# drvinput2.net
KiCad netlist of a schematic drawn in Altium Designer
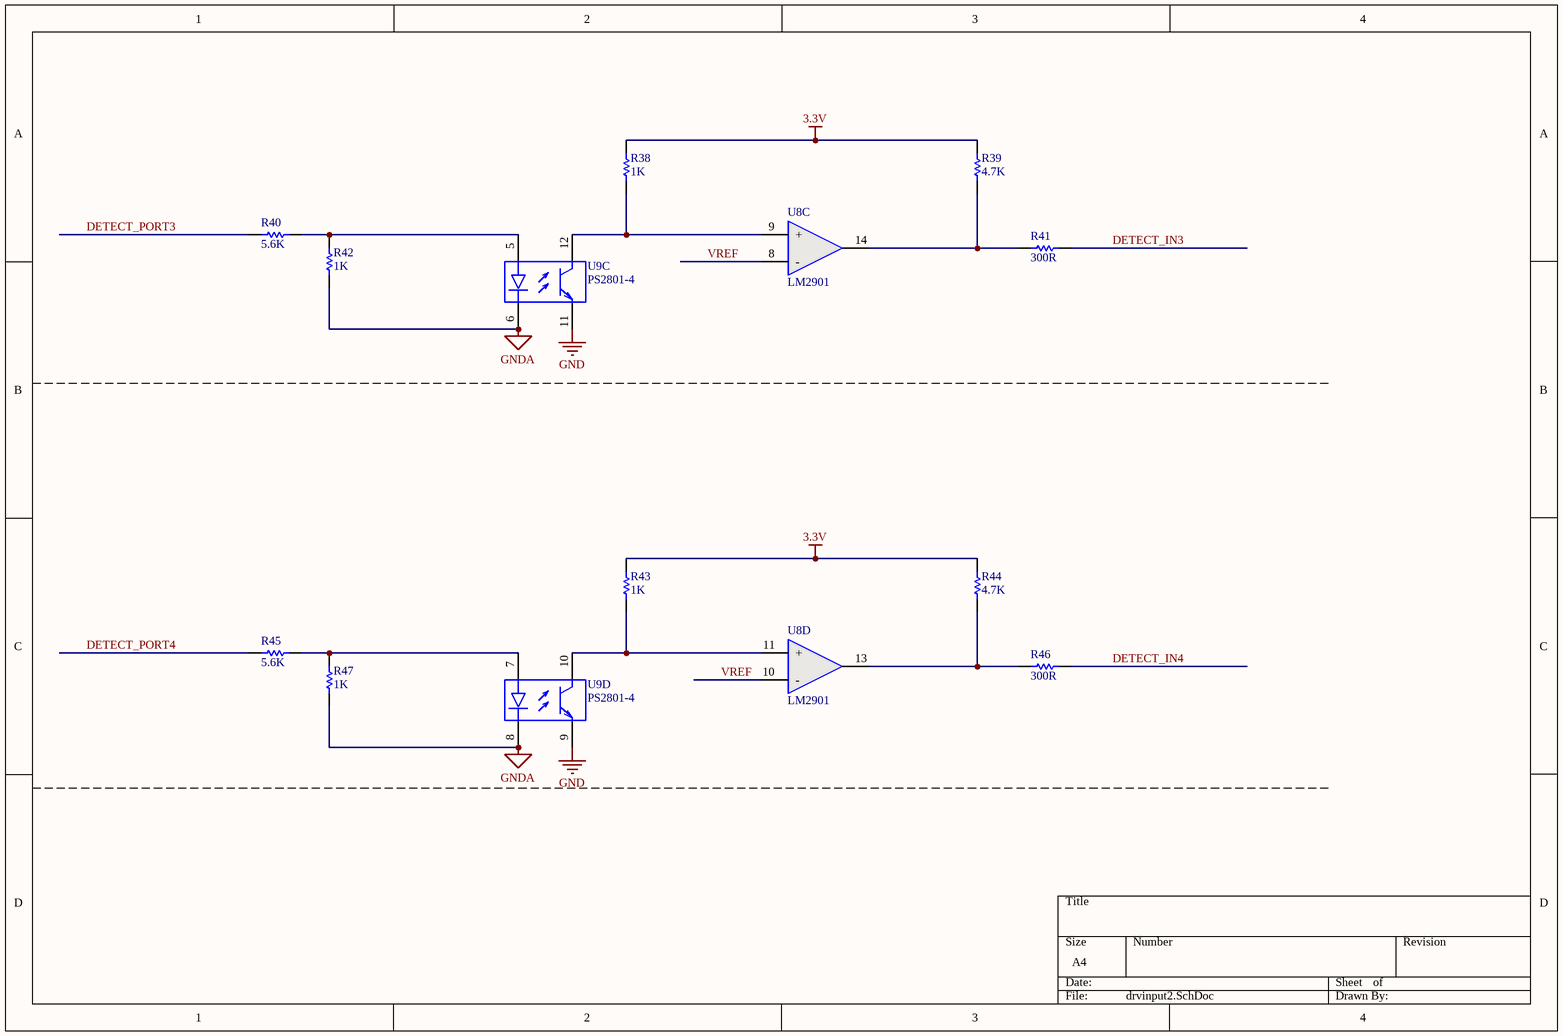
[diagram p0: drvinput2.SchDoc]

(export (version "E")
  (design (tool "Eeschema 10.0.6"))
  (components
    (comp (ref "R38")
      (value "1K")
      (footprint "RESC2012M")
      (description "Resistor")
      (fields (field (name "PUBLISHER") "Altium Limited"))
      (libsource (lib "Miscellaneous Devices") (part "Res1"))
    )
    (comp (ref "R39")
      (value "4.7K")
      (footprint "RESC2012M")
      (description "Resistor")
      (fields (field (name "PUBLISHER") "Altium Limited"))
      (libsource (lib "Miscellaneous Devices") (part "Res1"))
    )
    (comp (ref "R40")
      (value "5.6K")
      (footprint "RESC2012M")
      (description "Resistor")
      (fields (field (name "PUBLISHER") "Altium Limited"))
      (libsource (lib "Miscellaneous Devices") (part "Res1"))
    )
    (comp (ref "R41")
      (value "300R")
      (footprint "RESC2012M")
      (description "Resistor")
      (fields (field (name "PUBLISHER") "Altium Limited"))
      (libsource (lib "Miscellaneous Devices") (part "Res1"))
    )
    (comp (ref "R42")
      (value "1K")
      (footprint "RESC2012M")
      (description "Resistor")
      (fields (field (name "PUBLISHER") "Altium Limited"))
      (libsource (lib "Miscellaneous Devices") (part "Res1"))
    )
    (comp (ref "R43")
      (value "1K")
      (footprint "RESC2012M")
      (description "Resistor")
      (fields (field (name "PUBLISHER") "Altium Limited"))
      (libsource (lib "Miscellaneous Devices") (part "Res1"))
    )
    (comp (ref "R44")
      (value "4.7K")
      (footprint "RESC2012M")
      (description "Resistor")
      (fields (field (name "PUBLISHER") "Altium Limited"))
      (libsource (lib "Miscellaneous Devices") (part "Res1"))
    )
    (comp (ref "R45")
      (value "5.6K")
      (footprint "RESC2012M")
      (description "Resistor")
      (fields (field (name "PUBLISHER") "Altium Limited"))
      (libsource (lib "Miscellaneous Devices") (part "Res1"))
    )
    (comp (ref "R46")
      (value "300R")
      (footprint "RESC2012M")
      (description "Resistor")
      (fields (field (name "PUBLISHER") "Altium Limited"))
      (libsource (lib "Miscellaneous Devices") (part "Res1"))
    )
    (comp (ref "R47")
      (value "1K")
      (footprint "RESC2012M")
      (description "Resistor")
      (fields (field (name "PUBLISHER") "Altium Limited"))
      (libsource (lib "Miscellaneous Devices") (part "Res1"))
    )
    (comp (ref "U8")
      (value "LM2901")
      (footprint "SOIC-14AM")
      (description "4通道差分比较器芯片")
      (libsource (lib "UserSchDev") (part "LM2901"))
    )
    (comp (ref "U9")
      (value "PS2801-4")
      (footprint "SOIC16_N")
      (fields (field (name "PUBLISHER") "Altium Limited"))
      (libsource (lib "UserSchDev") (part "PS2801-4"))
    )
  )
  (nets
    (net (code "1") (name "/DETECT_IN3") (class "Default")
      (node (ref "R41") (pin "1") (pinfunction "1_1") (pintype "passive"))
    )
    (net (code "2") (name "/DETECT_IN4") (class "Default")
      (node (ref "R46") (pin "2") (pinfunction "2_2") (pintype "passive"))
    )
    (net (code "3") (name "/DETECT_PORT3") (class "Default")
      (node (ref "R40") (pin "2") (pinfunction "2_2") (pintype "passive"))
    )
    (net (code "4") (name "/DETECT_PORT4") (class "Default")
      (node (ref "R45") (pin "2") (pinfunction "2_2") (pintype "passive"))
    )
    (net (code "5") (name "/VREF") (class "Default")
      (node (ref "U8") (pin "10") (pinfunction "-_10") (pintype "passive"))
      (node (ref "U8") (pin "8") (pinfunction "-_8") (pintype "passive"))
    )
    (net (code "6") (name "3.3V") (class "Default")
      (node (ref "R38") (pin "1") (pinfunction "1_1") (pintype "passive"))
      (node (ref "R39") (pin "2") (pinfunction "2_2") (pintype "passive"))
      (node (ref "R43") (pin "1") (pinfunction "1_1") (pintype "passive"))
      (node (ref "R44") (pin "2") (pinfunction "2_2") (pintype "passive"))
    )
    (net (code "7") (name "GND") (class "Default")
      (node (ref "U9") (pin "11") (pinfunction "E_11") (pintype "passive"))
      (node (ref "U9") (pin "9") (pinfunction "E_9") (pintype "passive"))
    )
    (net (code "8") (name "GNDA") (class "Default")
      (node (ref "R42") (pin "1") (pinfunction "1_1") (pintype "passive"))
      (node (ref "R47") (pin "1") (pinfunction "1_1") (pintype "passive"))
      (node (ref "U9") (pin "6") (pinfunction "-_6") (pintype "passive"))
      (node (ref "U9") (pin "8") (pinfunction "-_8") (pintype "passive"))
    )
    (net (code "9") (name "Net-(U8C-+)") (class "Default")
      (node (ref "R38") (pin "2") (pinfunction "2_2") (pintype "passive"))
      (node (ref "U8") (pin "9") (pinfunction "+_9") (pintype "passive"))
      (node (ref "U9") (pin "12") (pinfunction "C_12") (pintype "passive"))
    )
    (net (code "10") (name "Net-(U8C-OUT)") (class "Default")
      (node (ref "R39") (pin "1") (pinfunction "1_1") (pintype "passive"))
      (node (ref "R41") (pin "2") (pinfunction "2_2") (pintype "passive"))
      (node (ref "U8") (pin "14") (pinfunction "OUT_14") (pintype "passive"))
    )
    (net (code "11") (name "Net-(U8D-+)") (class "Default")
      (node (ref "R43") (pin "2") (pinfunction "2_2") (pintype "passive"))
      (node (ref "U8") (pin "11") (pinfunction "+_11") (pintype "passive"))
      (node (ref "U9") (pin "10") (pinfunction "C_10") (pintype "passive"))
    )
    (net (code "12") (name "Net-(U8D-OUT)") (class "Default")
      (node (ref "R44") (pin "1") (pinfunction "1_1") (pintype "passive"))
      (node (ref "R46") (pin "1") (pinfunction "1_1") (pintype "passive"))
      (node (ref "U8") (pin "13") (pinfunction "OUT_13") (pintype "passive"))
    )
    (net (code "13") (name "Net-(U9C-+)") (class "Default")
      (node (ref "R40") (pin "1") (pinfunction "1_1") (pintype "passive"))
      (node (ref "R42") (pin "2") (pinfunction "2_2") (pintype "passive"))
      (node (ref "U9") (pin "5") (pinfunction "+_5") (pintype "passive"))
    )
    (net (code "14") (name "Net-(U9D-+)") (class "Default")
      (node (ref "R45") (pin "1") (pinfunction "1_1") (pintype "passive"))
      (node (ref "R47") (pin "2") (pinfunction "2_2") (pintype "passive"))
      (node (ref "U9") (pin "7") (pinfunction "+_7") (pintype "passive"))
    )
  )
)
